# Sheet1.net
KiCad netlist of a schematic drawn in Altium Designer
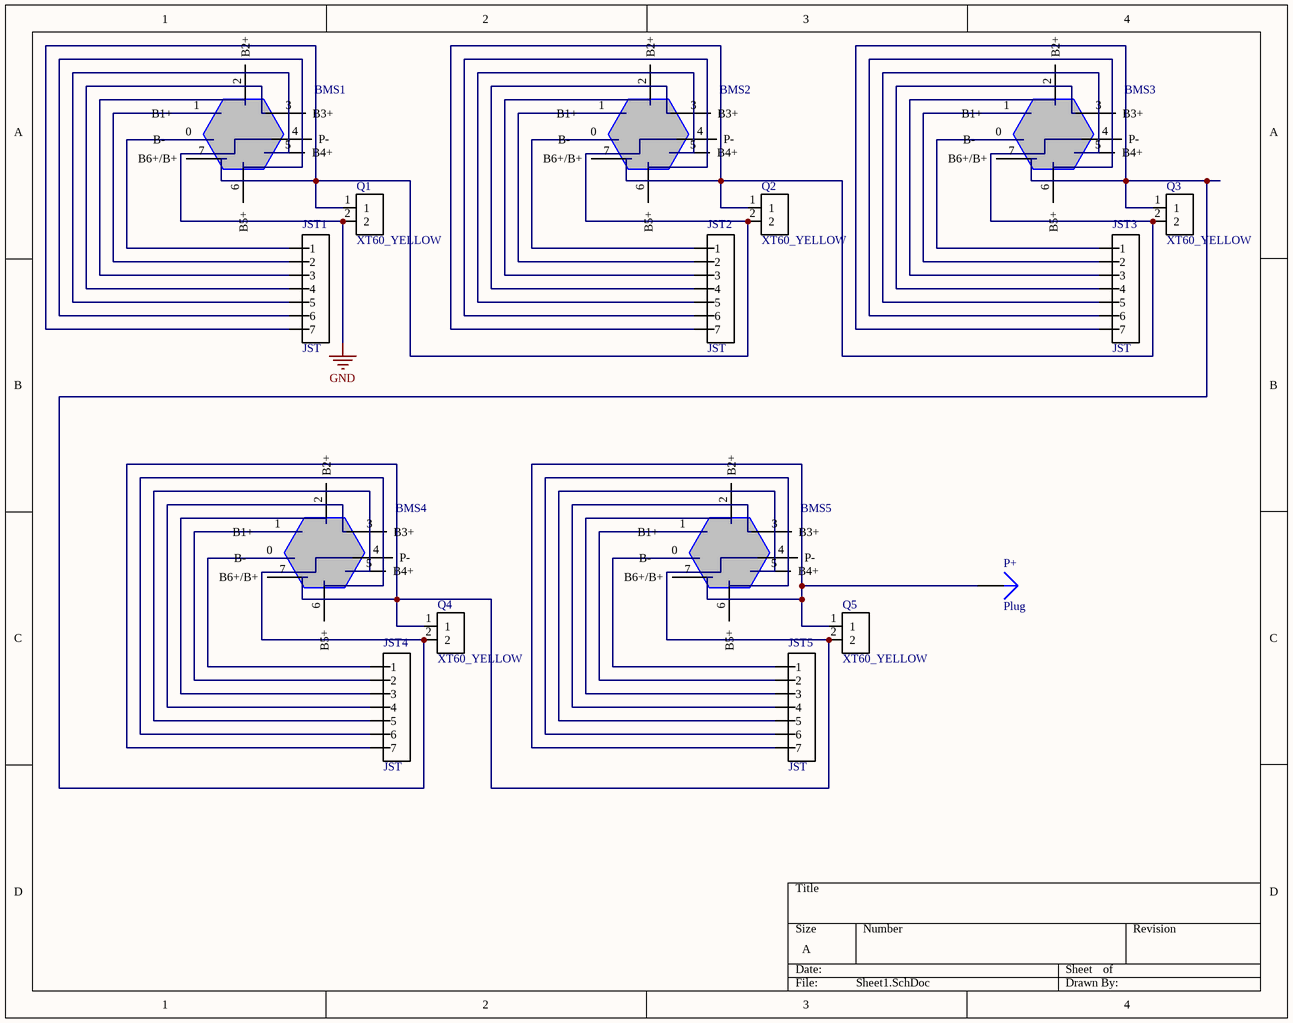
[diagram p0: Sheet1.SchDoc]

(export (version "E")
  (design (tool "Eeschema 10.0.6"))
  (components
    (comp (ref "BMS1")
      (value "BMS")
      (footprint "BMS")
      (description "Battery Management System")
      (libsource (lib "Power_PCB") (part "BMS"))
    )
    (comp (ref "BMS2")
      (value "BMS")
      (footprint "BMS")
      (description "Battery Management System")
      (libsource (lib "Power_PCB") (part "BMS"))
    )
    (comp (ref "BMS3")
      (value "BMS")
      (footprint "BMS")
      (description "Battery Management System")
      (libsource (lib "Power_PCB") (part "BMS"))
    )
    (comp (ref "BMS4")
      (value "BMS")
      (footprint "BMS")
      (description "Battery Management System")
      (libsource (lib "Power_PCB") (part "BMS"))
    )
    (comp (ref "BMS5")
      (value "BMS")
      (footprint "BMS")
      (description "Battery Management System")
      (libsource (lib "Power_PCB") (part "BMS"))
    )
    (comp (ref "JST1")
      (value "JST")
      (footprint "JST")
      (description "Connector Header Through Hole, Right Angle 7 position 0.098 _2.50mm_")
      (fields (field (name "MF") "JST Sales") (field (name "MP") "S7B-XH-A_LF__SN_"))
      (libsource (lib "Power_PCB") (part "JST"))
    )
    (comp (ref "JST2")
      (value "JST")
      (footprint "JST")
      (description "Connector Header Through Hole, Right Angle 7 position 0.098 _2.50mm_")
      (fields (field (name "MF") "JST Sales") (field (name "MP") "S7B-XH-A_LF__SN_"))
      (libsource (lib "Power_PCB") (part "JST"))
    )
    (comp (ref "JST3")
      (value "JST")
      (footprint "JST")
      (description "Connector Header Through Hole, Right Angle 7 position 0.098 _2.50mm_")
      (fields (field (name "MF") "JST Sales") (field (name "MP") "S7B-XH-A_LF__SN_"))
      (libsource (lib "Power_PCB") (part "JST"))
    )
    (comp (ref "JST4")
      (value "JST")
      (footprint "JST")
      (description "Connector Header Through Hole, Right Angle 7 position 0.098 _2.50mm_")
      (fields (field (name "MF") "JST Sales") (field (name "MP") "S7B-XH-A_LF__SN_"))
      (libsource (lib "Power_PCB") (part "JST"))
    )
    (comp (ref "JST5")
      (value "JST")
      (footprint "JST")
      (description "Connector Header Through Hole, Right Angle 7 position 0.098 _2.50mm_")
      (fields (field (name "MF") "JST Sales") (field (name "MP") "S7B-XH-A_LF__SN_"))
      (libsource (lib "Power_PCB") (part "JST"))
    )
    (comp (ref "P+")
      (value "Plug")
      (footprint "PIN1")
      (fields (field (name "PUBLISHER") "Altium Limited"))
      (libsource (lib "Miscellaneous Connectors") (part "Plug"))
    )
    (comp (ref "Q1")
      (value "XT60_YELLOW")
      (footprint "*AMASS_XT60PB-M")
      (description "Power connector; 65A; PIN: 2; Colour: yellow")
      (fields (field (name "MF") "Pololu") (field (name "MP") "XT60 YELLOW"))
      (libsource (lib "Power_PCB") (part "EC3"))
    )
    (comp (ref "Q2")
      (value "XT60_YELLOW")
      (footprint "*AMASS_XT60PB-M")
      (description "Power connector; 65A; PIN: 2; Colour: yellow")
      (fields (field (name "MF") "Pololu") (field (name "MP") "XT60 YELLOW"))
      (libsource (lib "Power_PCB") (part "EC3"))
    )
    (comp (ref "Q3")
      (value "XT60_YELLOW")
      (footprint "*AMASS_XT60PB-M")
      (description "Power connector; 65A; PIN: 2; Colour: yellow")
      (fields (field (name "MF") "Pololu") (field (name "MP") "XT60 YELLOW"))
      (libsource (lib "Power_PCB") (part "EC3"))
    )
    (comp (ref "Q4")
      (value "XT60_YELLOW")
      (footprint "*AMASS_XT60PB-M")
      (description "Power connector; 65A; PIN: 2; Colour: yellow")
      (fields (field (name "MF") "Pololu") (field (name "MP") "XT60 YELLOW"))
      (libsource (lib "Power_PCB") (part "EC3"))
    )
    (comp (ref "Q5")
      (value "XT60_YELLOW")
      (footprint "*AMASS_XT60PB-M")
      (description "Power connector; 65A; PIN: 2; Colour: yellow")
      (fields (field (name "MF") "Pololu") (field (name "MP") "XT60 YELLOW"))
      (libsource (lib "Power_PCB") (part "EC3"))
    )
  )
  (nets
    (net (code "1") (name "GND") (class "Default")
      (node (ref "BMS1") (pin "4") (pinfunction "P-_4") (pintype "passive"))
      (node (ref "Q1") (pin "2") (pinfunction "2_2") (pintype "passive"))
    )
    (net (code "2") (name "Net-(BMS1-B-)") (class "Default")
      (node (ref "BMS1") (pin "0") (pinfunction "B-_0") (pintype "power_in"))
      (node (ref "JST1") (pin "1") (pinfunction "1_1") (pintype "passive"))
    )
    (net (code "3") (name "Net-(BMS1-B1+)") (class "Default")
      (node (ref "BMS1") (pin "1") (pinfunction "B1+_1") (pintype "passive"))
      (node (ref "JST1") (pin "2") (pinfunction "2_2") (pintype "passive"))
    )
    (net (code "4") (name "Net-(BMS1-B2+)") (class "Default")
      (node (ref "BMS1") (pin "2") (pinfunction "B2+_2") (pintype "passive"))
      (node (ref "JST1") (pin "3") (pinfunction "3_3") (pintype "passive"))
    )
    (net (code "5") (name "Net-(BMS1-B3+)") (class "Default")
      (node (ref "BMS1") (pin "3") (pinfunction "B3+_3") (pintype "passive"))
      (node (ref "JST1") (pin "4") (pinfunction "4_4") (pintype "passive"))
    )
    (net (code "6") (name "Net-(BMS1-B4+)") (class "Default")
      (node (ref "BMS1") (pin "5") (pinfunction "B4+_5") (pintype "passive"))
      (node (ref "JST1") (pin "5") (pinfunction "5_5") (pintype "passive"))
    )
    (net (code "7") (name "Net-(BMS1-B5+)") (class "Default")
      (node (ref "BMS1") (pin "6") (pinfunction "B5+_6") (pintype "passive"))
      (node (ref "JST1") (pin "6") (pinfunction "6_6") (pintype "passive"))
    )
    (net (code "8") (name "Net-(BMS1-B6+{slash}B+)") (class "Default")
      (node (ref "BMS1") (pin "7") (pinfunction "B6+/B+_7") (pintype "passive"))
      (node (ref "BMS2") (pin "4") (pinfunction "P-_4") (pintype "passive"))
      (node (ref "JST1") (pin "7") (pinfunction "7_7") (pintype "passive"))
      (node (ref "Q1") (pin "1") (pinfunction "1_1") (pintype "passive"))
      (node (ref "Q2") (pin "2") (pinfunction "2_2") (pintype "passive"))
    )
    (net (code "9") (name "Net-(BMS2-B-)") (class "Default")
      (node (ref "BMS2") (pin "0") (pinfunction "B-_0") (pintype "power_in"))
      (node (ref "JST2") (pin "1") (pinfunction "1_1") (pintype "passive"))
    )
    (net (code "10") (name "Net-(BMS2-B1+)") (class "Default")
      (node (ref "BMS2") (pin "1") (pinfunction "B1+_1") (pintype "passive"))
      (node (ref "JST2") (pin "2") (pinfunction "2_2") (pintype "passive"))
    )
    (net (code "11") (name "Net-(BMS2-B2+)") (class "Default")
      (node (ref "BMS2") (pin "2") (pinfunction "B2+_2") (pintype "passive"))
      (node (ref "JST2") (pin "3") (pinfunction "3_3") (pintype "passive"))
    )
    (net (code "12") (name "Net-(BMS2-B3+)") (class "Default")
      (node (ref "BMS2") (pin "3") (pinfunction "B3+_3") (pintype "passive"))
      (node (ref "JST2") (pin "4") (pinfunction "4_4") (pintype "passive"))
    )
    (net (code "13") (name "Net-(BMS2-B4+)") (class "Default")
      (node (ref "BMS2") (pin "5") (pinfunction "B4+_5") (pintype "passive"))
      (node (ref "JST2") (pin "5") (pinfunction "5_5") (pintype "passive"))
    )
    (net (code "14") (name "Net-(BMS2-B5+)") (class "Default")
      (node (ref "BMS2") (pin "6") (pinfunction "B5+_6") (pintype "passive"))
      (node (ref "JST2") (pin "6") (pinfunction "6_6") (pintype "passive"))
    )
    (net (code "15") (name "Net-(BMS2-B6+{slash}B+)") (class "Default")
      (node (ref "BMS2") (pin "7") (pinfunction "B6+/B+_7") (pintype "passive"))
      (node (ref "BMS3") (pin "4") (pinfunction "P-_4") (pintype "passive"))
      (node (ref "JST2") (pin "7") (pinfunction "7_7") (pintype "passive"))
      (node (ref "Q2") (pin "1") (pinfunction "1_1") (pintype "passive"))
      (node (ref "Q3") (pin "2") (pinfunction "2_2") (pintype "passive"))
    )
    (net (code "16") (name "Net-(BMS3-B-)") (class "Default")
      (node (ref "BMS3") (pin "0") (pinfunction "B-_0") (pintype "power_in"))
      (node (ref "JST3") (pin "1") (pinfunction "1_1") (pintype "passive"))
    )
    (net (code "17") (name "Net-(BMS3-B1+)") (class "Default")
      (node (ref "BMS3") (pin "1") (pinfunction "B1+_1") (pintype "passive"))
      (node (ref "JST3") (pin "2") (pinfunction "2_2") (pintype "passive"))
    )
    (net (code "18") (name "Net-(BMS3-B2+)") (class "Default")
      (node (ref "BMS3") (pin "2") (pinfunction "B2+_2") (pintype "passive"))
      (node (ref "JST3") (pin "3") (pinfunction "3_3") (pintype "passive"))
    )
    (net (code "19") (name "Net-(BMS3-B3+)") (class "Default")
      (node (ref "BMS3") (pin "3") (pinfunction "B3+_3") (pintype "passive"))
      (node (ref "JST3") (pin "4") (pinfunction "4_4") (pintype "passive"))
    )
    (net (code "20") (name "Net-(BMS3-B4+)") (class "Default")
      (node (ref "BMS3") (pin "5") (pinfunction "B4+_5") (pintype "passive"))
      (node (ref "JST3") (pin "5") (pinfunction "5_5") (pintype "passive"))
    )
    (net (code "21") (name "Net-(BMS3-B5+)") (class "Default")
      (node (ref "BMS3") (pin "6") (pinfunction "B5+_6") (pintype "passive"))
      (node (ref "JST3") (pin "6") (pinfunction "6_6") (pintype "passive"))
    )
    (net (code "22") (name "Net-(BMS3-B6+{slash}B+)") (class "Default")
      (node (ref "BMS3") (pin "7") (pinfunction "B6+/B+_7") (pintype "passive"))
      (node (ref "BMS4") (pin "4") (pinfunction "P-_4") (pintype "passive"))
      (node (ref "JST3") (pin "7") (pinfunction "7_7") (pintype "passive"))
      (node (ref "Q3") (pin "1") (pinfunction "1_1") (pintype "passive"))
      (node (ref "Q4") (pin "2") (pinfunction "2_2") (pintype "passive"))
    )
    (net (code "23") (name "Net-(BMS4-B-)") (class "Default")
      (node (ref "BMS4") (pin "0") (pinfunction "B-_0") (pintype "power_in"))
      (node (ref "JST4") (pin "1") (pinfunction "1_1") (pintype "passive"))
    )
    (net (code "24") (name "Net-(BMS4-B1+)") (class "Default")
      (node (ref "BMS4") (pin "1") (pinfunction "B1+_1") (pintype "passive"))
      (node (ref "JST4") (pin "2") (pinfunction "2_2") (pintype "passive"))
    )
    (net (code "25") (name "Net-(BMS4-B2+)") (class "Default")
      (node (ref "BMS4") (pin "2") (pinfunction "B2+_2") (pintype "passive"))
      (node (ref "JST4") (pin "3") (pinfunction "3_3") (pintype "passive"))
    )
    (net (code "26") (name "Net-(BMS4-B3+)") (class "Default")
      (node (ref "BMS4") (pin "3") (pinfunction "B3+_3") (pintype "passive"))
      (node (ref "JST4") (pin "4") (pinfunction "4_4") (pintype "passive"))
    )
    (net (code "27") (name "Net-(BMS4-B4+)") (class "Default")
      (node (ref "BMS4") (pin "5") (pinfunction "B4+_5") (pintype "passive"))
      (node (ref "JST4") (pin "5") (pinfunction "5_5") (pintype "passive"))
    )
    (net (code "28") (name "Net-(BMS4-B5+)") (class "Default")
      (node (ref "BMS4") (pin "6") (pinfunction "B5+_6") (pintype "passive"))
      (node (ref "JST4") (pin "6") (pinfunction "6_6") (pintype "passive"))
    )
    (net (code "29") (name "Net-(BMS4-B6+{slash}B+)") (class "Default")
      (node (ref "BMS4") (pin "7") (pinfunction "B6+/B+_7") (pintype "passive"))
      (node (ref "BMS5") (pin "4") (pinfunction "P-_4") (pintype "passive"))
      (node (ref "JST4") (pin "7") (pinfunction "7_7") (pintype "passive"))
      (node (ref "Q4") (pin "1") (pinfunction "1_1") (pintype "passive"))
      (node (ref "Q5") (pin "2") (pinfunction "2_2") (pintype "passive"))
    )
    (net (code "30") (name "Net-(BMS5-B-)") (class "Default")
      (node (ref "BMS5") (pin "0") (pinfunction "B-_0") (pintype "power_in"))
      (node (ref "JST5") (pin "1") (pinfunction "1_1") (pintype "passive"))
    )
    (net (code "31") (name "Net-(BMS5-B1+)") (class "Default")
      (node (ref "BMS5") (pin "1") (pinfunction "B1+_1") (pintype "passive"))
      (node (ref "JST5") (pin "2") (pinfunction "2_2") (pintype "passive"))
    )
    (net (code "32") (name "Net-(BMS5-B2+)") (class "Default")
      (node (ref "BMS5") (pin "2") (pinfunction "B2+_2") (pintype "passive"))
      (node (ref "JST5") (pin "3") (pinfunction "3_3") (pintype "passive"))
    )
    (net (code "33") (name "Net-(BMS5-B3+)") (class "Default")
      (node (ref "BMS5") (pin "3") (pinfunction "B3+_3") (pintype "passive"))
      (node (ref "JST5") (pin "4") (pinfunction "4_4") (pintype "passive"))
    )
    (net (code "34") (name "Net-(BMS5-B4+)") (class "Default")
      (node (ref "BMS5") (pin "5") (pinfunction "B4+_5") (pintype "passive"))
      (node (ref "JST5") (pin "5") (pinfunction "5_5") (pintype "passive"))
    )
    (net (code "35") (name "Net-(BMS5-B5+)") (class "Default")
      (node (ref "BMS5") (pin "6") (pinfunction "B5+_6") (pintype "passive"))
      (node (ref "JST5") (pin "6") (pinfunction "6_6") (pintype "passive"))
    )
    (net (code "36") (name "Net-(BMS5-B6+{slash}B+)") (class "Default")
      (node (ref "BMS5") (pin "7") (pinfunction "B6+/B+_7") (pintype "passive"))
      (node (ref "JST5") (pin "7") (pinfunction "7_7") (pintype "passive"))
      (node (ref "P+") (pin "1") (pinfunction "1_1") (pintype "passive"))
      (node (ref "Q5") (pin "1") (pinfunction "1_1") (pintype "passive"))
    )
  )
)
